# GPIO_EXPANDER_LED.net
KiCad netlist of a schematic drawn in Altium Designer
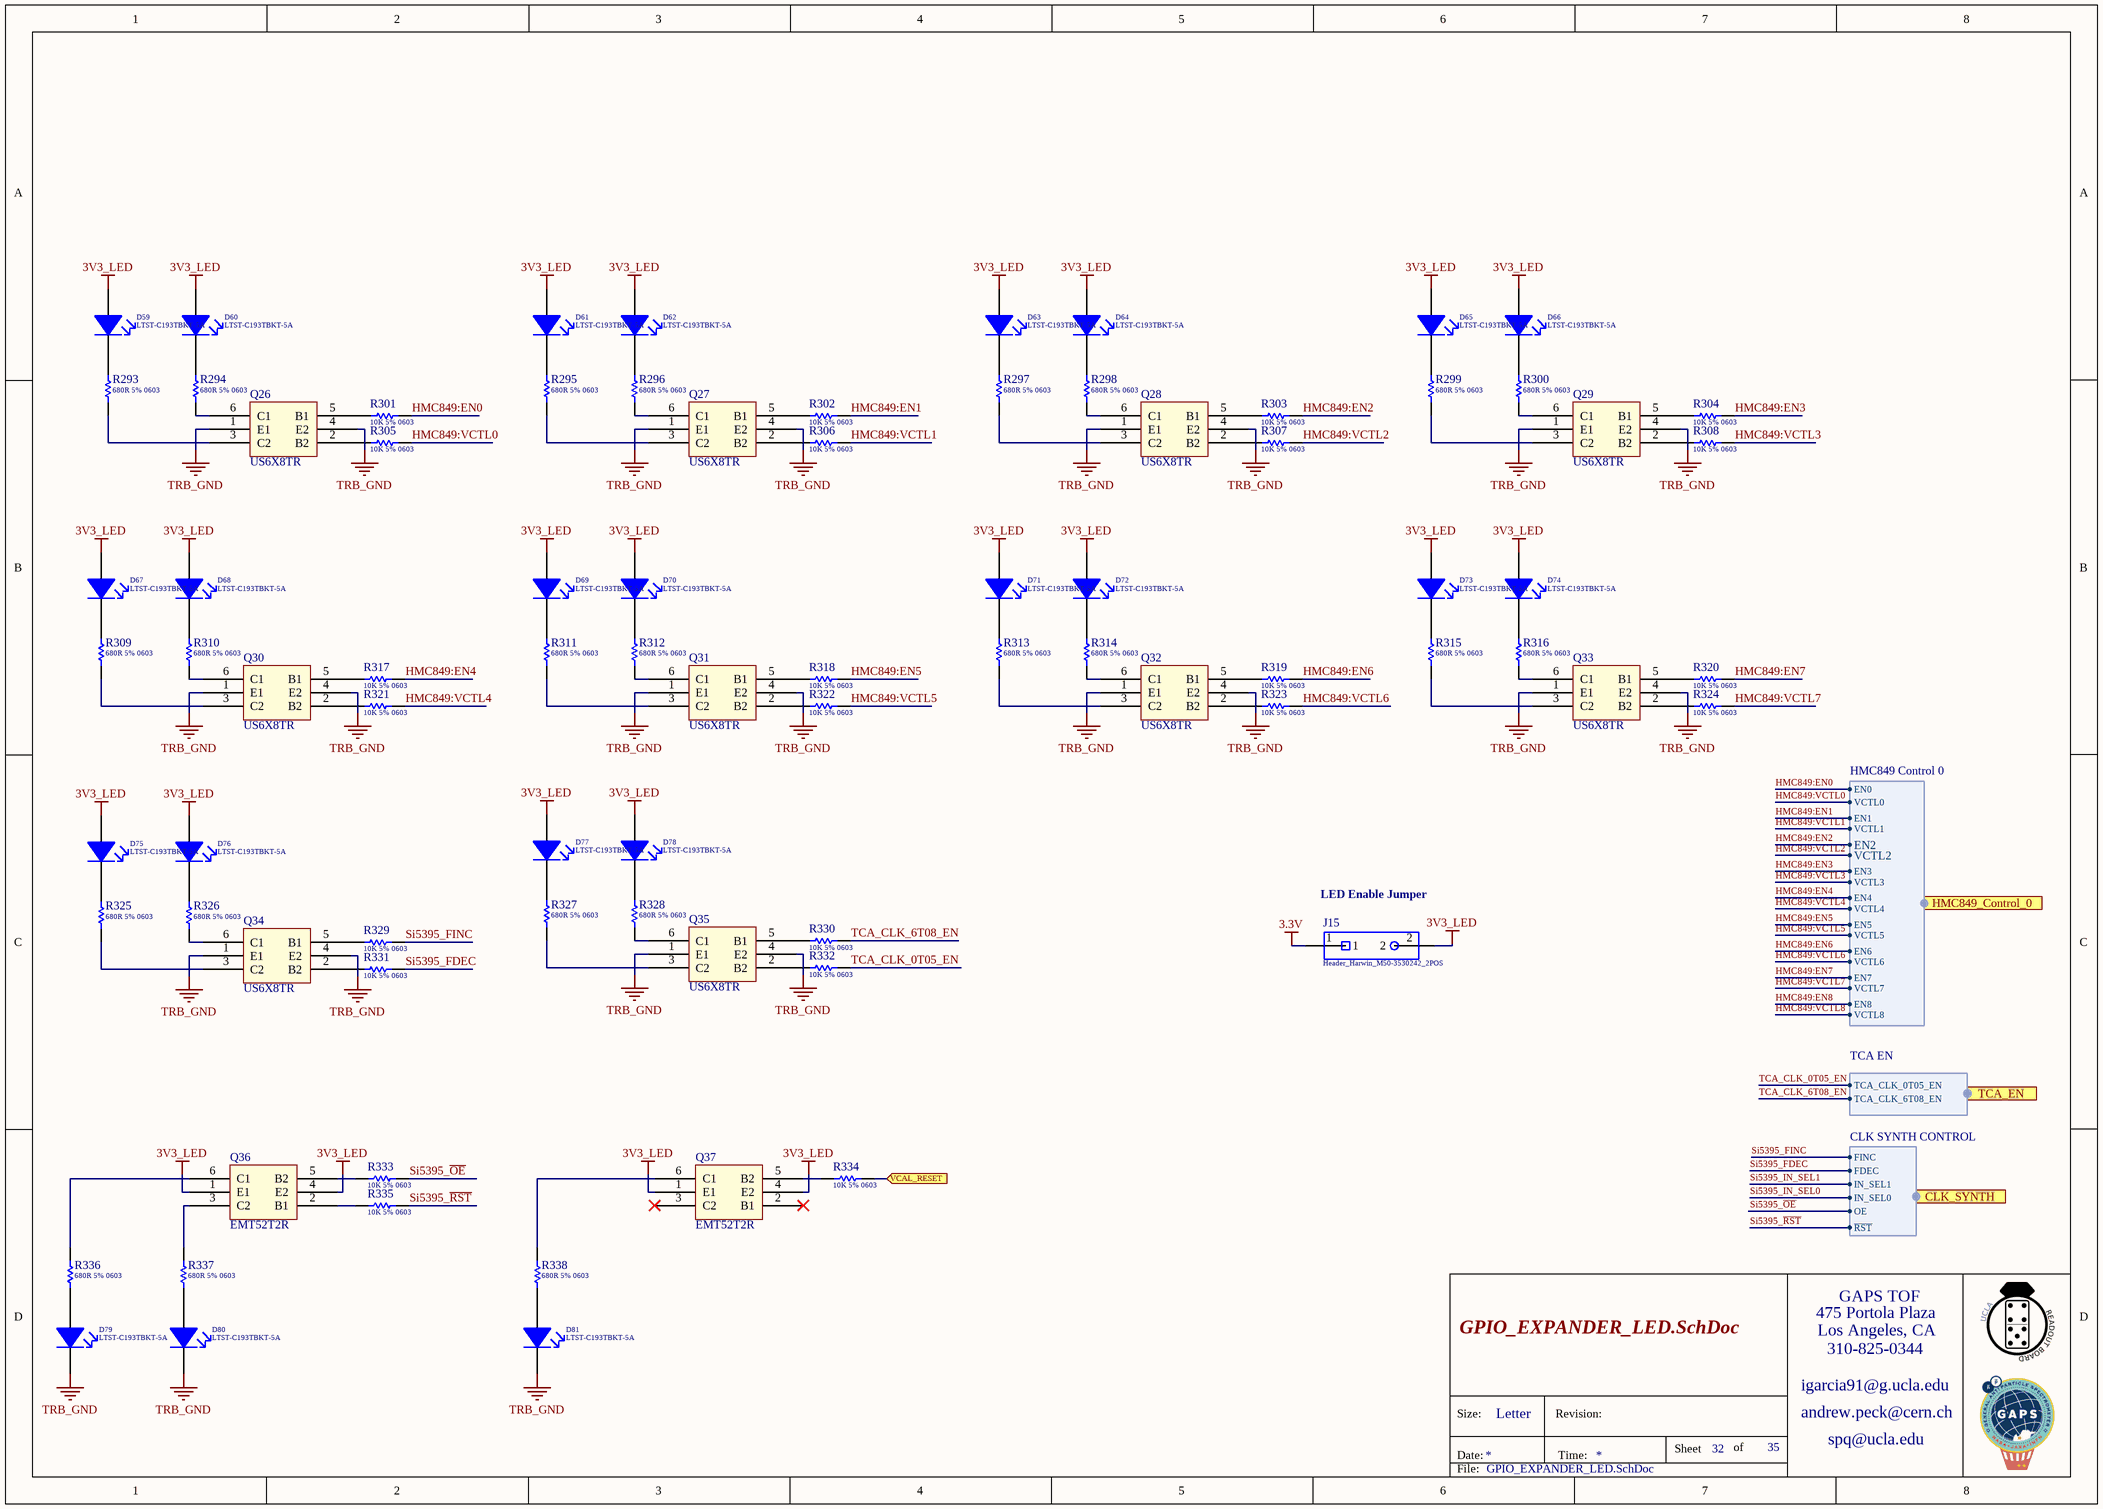
[diagram p0: GPIO_EXPANDER_LED.SchDoc]

(export (version "E")
  (design (tool "Eeschema 10.0.6"))
  (components
    (comp (ref "D59")
      (value "Led_Lite-On_LTST-C193TBKT-5A_Blue")
      (footprint "Led_Lite-On_LTST-C193TBKT-5A_Blue")
      (description "Standard LEDs - SMD Blue 470nm 28mcd 20mA")
      (fields (field (name "SERIES") "LTST-C193TBKT-5A"))
      (libsource (lib "Led_Lite-On_LTST-C193TBKT-5A_Blue") (part "Led_Lite-On_LTST-C193TBKT-5A_Blue"))
    )
    (comp (ref "D60")
      (value "Led_Lite-On_LTST-C193TBKT-5A_Blue")
      (footprint "Led_Lite-On_LTST-C193TBKT-5A_Blue")
      (description "Standard LEDs - SMD Blue 470nm 28mcd 20mA")
      (fields (field (name "SERIES") "LTST-C193TBKT-5A"))
      (libsource (lib "Led_Lite-On_LTST-C193TBKT-5A_Blue") (part "Led_Lite-On_LTST-C193TBKT-5A_Blue"))
    )
    (comp (ref "D61")
      (value "Led_Lite-On_LTST-C193TBKT-5A_Blue")
      (footprint "Led_Lite-On_LTST-C193TBKT-5A_Blue")
      (description "Standard LEDs - SMD Blue 470nm 28mcd 20mA")
      (fields (field (name "SERIES") "LTST-C193TBKT-5A"))
      (libsource (lib "Led_Lite-On_LTST-C193TBKT-5A_Blue") (part "Led_Lite-On_LTST-C193TBKT-5A_Blue"))
    )
    (comp (ref "D62")
      (value "Led_Lite-On_LTST-C193TBKT-5A_Blue")
      (footprint "Led_Lite-On_LTST-C193TBKT-5A_Blue")
      (description "Standard LEDs - SMD Blue 470nm 28mcd 20mA")
      (fields (field (name "SERIES") "LTST-C193TBKT-5A"))
      (libsource (lib "Led_Lite-On_LTST-C193TBKT-5A_Blue") (part "Led_Lite-On_LTST-C193TBKT-5A_Blue"))
    )
    (comp (ref "D63")
      (value "Led_Lite-On_LTST-C193TBKT-5A_Blue")
      (footprint "Led_Lite-On_LTST-C193TBKT-5A_Blue")
      (description "Standard LEDs - SMD Blue 470nm 28mcd 20mA")
      (fields (field (name "SERIES") "LTST-C193TBKT-5A"))
      (libsource (lib "Led_Lite-On_LTST-C193TBKT-5A_Blue") (part "Led_Lite-On_LTST-C193TBKT-5A_Blue"))
    )
    (comp (ref "D64")
      (value "Led_Lite-On_LTST-C193TBKT-5A_Blue")
      (footprint "Led_Lite-On_LTST-C193TBKT-5A_Blue")
      (description "Standard LEDs - SMD Blue 470nm 28mcd 20mA")
      (fields (field (name "SERIES") "LTST-C193TBKT-5A"))
      (libsource (lib "Led_Lite-On_LTST-C193TBKT-5A_Blue") (part "Led_Lite-On_LTST-C193TBKT-5A_Blue"))
    )
    (comp (ref "D65")
      (value "Led_Lite-On_LTST-C193TBKT-5A_Blue")
      (footprint "Led_Lite-On_LTST-C193TBKT-5A_Blue")
      (description "Standard LEDs - SMD Blue 470nm 28mcd 20mA")
      (fields (field (name "SERIES") "LTST-C193TBKT-5A"))
      (libsource (lib "Led_Lite-On_LTST-C193TBKT-5A_Blue") (part "Led_Lite-On_LTST-C193TBKT-5A_Blue"))
    )
    (comp (ref "D66")
      (value "Led_Lite-On_LTST-C193TBKT-5A_Blue")
      (footprint "Led_Lite-On_LTST-C193TBKT-5A_Blue")
      (description "Standard LEDs - SMD Blue 470nm 28mcd 20mA")
      (fields (field (name "SERIES") "LTST-C193TBKT-5A"))
      (libsource (lib "Led_Lite-On_LTST-C193TBKT-5A_Blue") (part "Led_Lite-On_LTST-C193TBKT-5A_Blue"))
    )
    (comp (ref "D67")
      (value "Led_Lite-On_LTST-C193TBKT-5A_Blue")
      (footprint "Led_Lite-On_LTST-C193TBKT-5A_Blue")
      (description "Standard LEDs - SMD Blue 470nm 28mcd 20mA")
      (fields (field (name "SERIES") "LTST-C193TBKT-5A"))
      (libsource (lib "Led_Lite-On_LTST-C193TBKT-5A_Blue") (part "Led_Lite-On_LTST-C193TBKT-5A_Blue"))
    )
    (comp (ref "D68")
      (value "Led_Lite-On_LTST-C193TBKT-5A_Blue")
      (footprint "Led_Lite-On_LTST-C193TBKT-5A_Blue")
      (description "Standard LEDs - SMD Blue 470nm 28mcd 20mA")
      (fields (field (name "SERIES") "LTST-C193TBKT-5A"))
      (libsource (lib "Led_Lite-On_LTST-C193TBKT-5A_Blue") (part "Led_Lite-On_LTST-C193TBKT-5A_Blue"))
    )
    (comp (ref "D69")
      (value "Led_Lite-On_LTST-C193TBKT-5A_Blue")
      (footprint "Led_Lite-On_LTST-C193TBKT-5A_Blue")
      (description "Standard LEDs - SMD Blue 470nm 28mcd 20mA")
      (fields (field (name "SERIES") "LTST-C193TBKT-5A"))
      (libsource (lib "Led_Lite-On_LTST-C193TBKT-5A_Blue") (part "Led_Lite-On_LTST-C193TBKT-5A_Blue"))
    )
    (comp (ref "D70")
      (value "Led_Lite-On_LTST-C193TBKT-5A_Blue")
      (footprint "Led_Lite-On_LTST-C193TBKT-5A_Blue")
      (description "Standard LEDs - SMD Blue 470nm 28mcd 20mA")
      (fields (field (name "SERIES") "LTST-C193TBKT-5A"))
      (libsource (lib "Led_Lite-On_LTST-C193TBKT-5A_Blue") (part "Led_Lite-On_LTST-C193TBKT-5A_Blue"))
    )
    (comp (ref "D71")
      (value "Led_Lite-On_LTST-C193TBKT-5A_Blue")
      (footprint "Led_Lite-On_LTST-C193TBKT-5A_Blue")
      (description "Standard LEDs - SMD Blue 470nm 28mcd 20mA")
      (fields (field (name "SERIES") "LTST-C193TBKT-5A"))
      (libsource (lib "Led_Lite-On_LTST-C193TBKT-5A_Blue") (part "Led_Lite-On_LTST-C193TBKT-5A_Blue"))
    )
    (comp (ref "D72")
      (value "Led_Lite-On_LTST-C193TBKT-5A_Blue")
      (footprint "Led_Lite-On_LTST-C193TBKT-5A_Blue")
      (description "Standard LEDs - SMD Blue 470nm 28mcd 20mA")
      (fields (field (name "SERIES") "LTST-C193TBKT-5A"))
      (libsource (lib "Led_Lite-On_LTST-C193TBKT-5A_Blue") (part "Led_Lite-On_LTST-C193TBKT-5A_Blue"))
    )
    (comp (ref "D73")
      (value "Led_Lite-On_LTST-C193TBKT-5A_Blue")
      (footprint "Led_Lite-On_LTST-C193TBKT-5A_Blue")
      (description "Standard LEDs - SMD Blue 470nm 28mcd 20mA")
      (fields (field (name "SERIES") "LTST-C193TBKT-5A"))
      (libsource (lib "Led_Lite-On_LTST-C193TBKT-5A_Blue") (part "Led_Lite-On_LTST-C193TBKT-5A_Blue"))
    )
    (comp (ref "D74")
      (value "Led_Lite-On_LTST-C193TBKT-5A_Blue")
      (footprint "Led_Lite-On_LTST-C193TBKT-5A_Blue")
      (description "Standard LEDs - SMD Blue 470nm 28mcd 20mA")
      (fields (field (name "SERIES") "LTST-C193TBKT-5A"))
      (libsource (lib "Led_Lite-On_LTST-C193TBKT-5A_Blue") (part "Led_Lite-On_LTST-C193TBKT-5A_Blue"))
    )
    (comp (ref "D75")
      (value "Led_Lite-On_LTST-C193TBKT-5A_Blue")
      (footprint "Led_Lite-On_LTST-C193TBKT-5A_Blue")
      (description "Standard LEDs - SMD Blue 470nm 28mcd 20mA")
      (fields (field (name "SERIES") "LTST-C193TBKT-5A"))
      (libsource (lib "Led_Lite-On_LTST-C193TBKT-5A_Blue") (part "Led_Lite-On_LTST-C193TBKT-5A_Blue"))
    )
    (comp (ref "D76")
      (value "Led_Lite-On_LTST-C193TBKT-5A_Blue")
      (footprint "Led_Lite-On_LTST-C193TBKT-5A_Blue")
      (description "Standard LEDs - SMD Blue 470nm 28mcd 20mA")
      (fields (field (name "SERIES") "LTST-C193TBKT-5A"))
      (libsource (lib "Led_Lite-On_LTST-C193TBKT-5A_Blue") (part "Led_Lite-On_LTST-C193TBKT-5A_Blue"))
    )
    (comp (ref "D77")
      (value "Led_Lite-On_LTST-C193TBKT-5A_Blue")
      (footprint "Led_Lite-On_LTST-C193TBKT-5A_Blue")
      (description "Standard LEDs - SMD Blue 470nm 28mcd 20mA")
      (fields (field (name "SERIES") "LTST-C193TBKT-5A"))
      (libsource (lib "Led_Lite-On_LTST-C193TBKT-5A_Blue") (part "Led_Lite-On_LTST-C193TBKT-5A_Blue"))
    )
    (comp (ref "D78")
      (value "Led_Lite-On_LTST-C193TBKT-5A_Blue")
      (footprint "Led_Lite-On_LTST-C193TBKT-5A_Blue")
      (description "Standard LEDs - SMD Blue 470nm 28mcd 20mA")
      (fields (field (name "SERIES") "LTST-C193TBKT-5A"))
      (libsource (lib "Led_Lite-On_LTST-C193TBKT-5A_Blue") (part "Led_Lite-On_LTST-C193TBKT-5A_Blue"))
    )
    (comp (ref "D79")
      (value "Led_Lite-On_LTST-C193TBKT-5A_Blue")
      (footprint "Led_Lite-On_LTST-C193TBKT-5A_Blue")
      (description "Standard LEDs - SMD Blue 470nm 28mcd 20mA")
      (fields (field (name "SERIES") "LTST-C193TBKT-5A"))
      (libsource (lib "Led_Lite-On_LTST-C193TBKT-5A_Blue") (part "Led_Lite-On_LTST-C193TBKT-5A_Blue"))
    )
    (comp (ref "D80")
      (value "Led_Lite-On_LTST-C193TBKT-5A_Blue")
      (footprint "Led_Lite-On_LTST-C193TBKT-5A_Blue")
      (description "Standard LEDs - SMD Blue 470nm 28mcd 20mA")
      (fields (field (name "SERIES") "LTST-C193TBKT-5A"))
      (libsource (lib "Led_Lite-On_LTST-C193TBKT-5A_Blue") (part "Led_Lite-On_LTST-C193TBKT-5A_Blue"))
    )
    (comp (ref "D81")
      (value "Led_Lite-On_LTST-C193TBKT-5A_Blue")
      (footprint "Led_Lite-On_LTST-C193TBKT-5A_Blue")
      (description "Standard LEDs - SMD Blue 470nm 28mcd 20mA")
      (fields (field (name "SERIES") "LTST-C193TBKT-5A"))
      (libsource (lib "Led_Lite-On_LTST-C193TBKT-5A_Blue") (part "Led_Lite-On_LTST-C193TBKT-5A_Blue"))
    )
    (comp (ref "J15")
      (value "Header_Harwin_M50-3530242_2POS")
      (footprint "Header_Harwin_M50-3530242_2POS")
      (description "Headers & Wire Housings 2 WAY SIL VERT PC TAIL P/HDR")
      (libsource (lib "Header_Harwin_M50-3530242_2POS") (part "Header_Harwin_M50-3530242_2POS"))
    )
    (comp (ref "Q26")
      (value "BJT_ROHM_US6X8TR_1A_NPN")
      (footprint "BJT_ROHM_US6X8TR_1A_NPN")
      (description "Bipolar Transistors - BJT NPN+NPN 30VCEO 1A SOT-363T")
      (fields (field (name "SERIES") "US6X8TR"))
      (libsource (lib "BJT_ROHM_US6X8TR_1A_NPN") (part "BJT_ROHM_US6X8TR_1A_NPN"))
    )
    (comp (ref "Q27")
      (value "BJT_ROHM_US6X8TR_1A_NPN")
      (footprint "BJT_ROHM_US6X8TR_1A_NPN")
      (description "Bipolar Transistors - BJT NPN+NPN 30VCEO 1A SOT-363T")
      (fields (field (name "SERIES") "US6X8TR"))
      (libsource (lib "BJT_ROHM_US6X8TR_1A_NPN") (part "BJT_ROHM_US6X8TR_1A_NPN"))
    )
    (comp (ref "Q28")
      (value "BJT_ROHM_US6X8TR_1A_NPN")
      (footprint "BJT_ROHM_US6X8TR_1A_NPN")
      (description "Bipolar Transistors - BJT NPN+NPN 30VCEO 1A SOT-363T")
      (fields (field (name "SERIES") "US6X8TR"))
      (libsource (lib "BJT_ROHM_US6X8TR_1A_NPN") (part "BJT_ROHM_US6X8TR_1A_NPN"))
    )
    (comp (ref "Q29")
      (value "BJT_ROHM_US6X8TR_1A_NPN")
      (footprint "BJT_ROHM_US6X8TR_1A_NPN")
      (description "Bipolar Transistors - BJT NPN+NPN 30VCEO 1A SOT-363T")
      (fields (field (name "SERIES") "US6X8TR"))
      (libsource (lib "BJT_ROHM_US6X8TR_1A_NPN") (part "BJT_ROHM_US6X8TR_1A_NPN"))
    )
    (comp (ref "Q30")
      (value "BJT_ROHM_US6X8TR_1A_NPN")
      (footprint "BJT_ROHM_US6X8TR_1A_NPN")
      (description "Bipolar Transistors - BJT NPN+NPN 30VCEO 1A SOT-363T")
      (fields (field (name "SERIES") "US6X8TR"))
      (libsource (lib "BJT_ROHM_US6X8TR_1A_NPN") (part "BJT_ROHM_US6X8TR_1A_NPN"))
    )
    (comp (ref "Q31")
      (value "BJT_ROHM_US6X8TR_1A_NPN")
      (footprint "BJT_ROHM_US6X8TR_1A_NPN")
      (description "Bipolar Transistors - BJT NPN+NPN 30VCEO 1A SOT-363T")
      (fields (field (name "SERIES") "US6X8TR"))
      (libsource (lib "BJT_ROHM_US6X8TR_1A_NPN") (part "BJT_ROHM_US6X8TR_1A_NPN"))
    )
    (comp (ref "Q32")
      (value "BJT_ROHM_US6X8TR_1A_NPN")
      (footprint "BJT_ROHM_US6X8TR_1A_NPN")
      (description "Bipolar Transistors - BJT NPN+NPN 30VCEO 1A SOT-363T")
      (fields (field (name "SERIES") "US6X8TR"))
      (libsource (lib "BJT_ROHM_US6X8TR_1A_NPN") (part "BJT_ROHM_US6X8TR_1A_NPN"))
    )
    (comp (ref "Q33")
      (value "BJT_ROHM_US6X8TR_1A_NPN")
      (footprint "BJT_ROHM_US6X8TR_1A_NPN")
      (description "Bipolar Transistors - BJT NPN+NPN 30VCEO 1A SOT-363T")
      (fields (field (name "SERIES") "US6X8TR"))
      (libsource (lib "BJT_ROHM_US6X8TR_1A_NPN") (part "BJT_ROHM_US6X8TR_1A_NPN"))
    )
    (comp (ref "Q34")
      (value "BJT_ROHM_US6X8TR_1A_NPN")
      (footprint "BJT_ROHM_US6X8TR_1A_NPN")
      (description "Bipolar Transistors - BJT NPN+NPN 30VCEO 1A SOT-363T")
      (fields (field (name "SERIES") "US6X8TR"))
      (libsource (lib "BJT_ROHM_US6X8TR_1A_NPN") (part "BJT_ROHM_US6X8TR_1A_NPN"))
    )
    (comp (ref "Q35")
      (value "BJT_ROHM_US6X8TR_1A_NPN")
      (footprint "BJT_ROHM_US6X8TR_1A_NPN")
      (description "Bipolar Transistors - BJT NPN+NPN 30VCEO 1A SOT-363T")
      (fields (field (name "SERIES") "US6X8TR"))
      (libsource (lib "BJT_ROHM_US6X8TR_1A_NPN") (part "BJT_ROHM_US6X8TR_1A_NPN"))
    )
    (comp (ref "Q36")
      (value "BJT_ROHM_EMT52T2R_100mA_PNP")
      (footprint "BJT_ROHM_EMT52T2R_100mA_PNP")
      (description "Bipolar Transistors - BJT Bipolar Transistor SOT-563 SC-107C EMT6")
      (fields (field (name "SERIES") "EMT52T2R"))
      (libsource (lib "BJT_ROHM_EMT52T2R_100mA_PNP") (part "BJT_ROHM_EMT52T2R_100mA_PNP"))
    )
    (comp (ref "Q37")
      (value "BJT_ROHM_EMT52T2R_100mA_PNP")
      (footprint "BJT_ROHM_EMT52T2R_100mA_PNP")
      (description "Bipolar Transistors - BJT Bipolar Transistor SOT-563 SC-107C EMT6")
      (fields (field (name "SERIES") "EMT52T2R"))
      (libsource (lib "BJT_ROHM_EMT52T2R_100mA_PNP") (part "BJT_ROHM_EMT52T2R_100mA_PNP"))
    )
    (comp (ref "R293")
      (value "680R 5% 0603")
      (footprint "RESC0603(1608)_L")
      (description "680R 0.1W 5% 0603 (1608 Metric)  SMD")
      (fields (field (name "TOLERANCE") "5 %") (field (name "POWER") "0.1 W"))
      (libsource (lib "Altium Content Vault") (part "RES"))
    )
    (comp (ref "R294")
      (value "680R 5% 0603")
      (footprint "RESC0603(1608)_L")
      (description "680R 0.1W 5% 0603 (1608 Metric)  SMD")
      (fields (field (name "TOLERANCE") "5 %") (field (name "POWER") "0.1 W"))
      (libsource (lib "Altium Content Vault") (part "RES"))
    )
    (comp (ref "R295")
      (value "680R 5% 0603")
      (footprint "RESC0603(1608)_L")
      (description "680R 0.1W 5% 0603 (1608 Metric)  SMD")
      (fields (field (name "TOLERANCE") "5 %") (field (name "POWER") "0.1 W"))
      (libsource (lib "Altium Content Vault") (part "RES"))
    )
    (comp (ref "R296")
      (value "680R 5% 0603")
      (footprint "RESC0603(1608)_L")
      (description "680R 0.1W 5% 0603 (1608 Metric)  SMD")
      (fields (field (name "TOLERANCE") "5 %") (field (name "POWER") "0.1 W"))
      (libsource (lib "Altium Content Vault") (part "RES"))
    )
    (comp (ref "R297")
      (value "680R 5% 0603")
      (footprint "RESC0603(1608)_L")
      (description "680R 0.1W 5% 0603 (1608 Metric)  SMD")
      (fields (field (name "TOLERANCE") "5 %") (field (name "POWER") "0.1 W"))
      (libsource (lib "Altium Content Vault") (part "RES"))
    )
    (comp (ref "R298")
      (value "680R 5% 0603")
      (footprint "RESC0603(1608)_L")
      (description "680R 0.1W 5% 0603 (1608 Metric)  SMD")
      (fields (field (name "TOLERANCE") "5 %") (field (name "POWER") "0.1 W"))
      (libsource (lib "Altium Content Vault") (part "RES"))
    )
    (comp (ref "R299")
      (value "680R 5% 0603")
      (footprint "RESC0603(1608)_L")
      (description "680R 0.1W 5% 0603 (1608 Metric)  SMD")
      (fields (field (name "TOLERANCE") "5 %") (field (name "POWER") "0.1 W"))
      (libsource (lib "Altium Content Vault") (part "RES"))
    )
    (comp (ref "R300")
      (value "680R 5% 0603")
      (footprint "RESC0603(1608)_L")
      (description "680R 0.1W 5% 0603 (1608 Metric)  SMD")
      (fields (field (name "TOLERANCE") "5 %") (field (name "POWER") "0.1 W"))
      (libsource (lib "Altium Content Vault") (part "RES"))
    )
    (comp (ref "R301")
      (value "10K 5% 0603")
      (footprint "RESC0603(1608)_L")
      (description "10K 0.1W 5% 0603 (1608 Metric)  SMD")
      (fields (field (name "TOLERANCE") "5 %") (field (name "POWER") "0.1 W"))
      (libsource (lib "Altium Content Vault") (part "RES"))
    )
    (comp (ref "R302")
      (value "10K 5% 0603")
      (footprint "RESC0603(1608)_L")
      (description "10K 0.1W 5% 0603 (1608 Metric)  SMD")
      (fields (field (name "TOLERANCE") "5 %") (field (name "POWER") "0.1 W"))
      (libsource (lib "Altium Content Vault") (part "RES"))
    )
    (comp (ref "R303")
      (value "10K 5% 0603")
      (footprint "RESC0603(1608)_L")
      (description "10K 0.1W 5% 0603 (1608 Metric)  SMD")
      (fields (field (name "TOLERANCE") "5 %") (field (name "POWER") "0.1 W"))
      (libsource (lib "Altium Content Vault") (part "RES"))
    )
    (comp (ref "R304")
      (value "10K 5% 0603")
      (footprint "RESC0603(1608)_L")
      (description "10K 0.1W 5% 0603 (1608 Metric)  SMD")
      (fields (field (name "TOLERANCE") "5 %") (field (name "POWER") "0.1 W"))
      (libsource (lib "Altium Content Vault") (part "RES"))
    )
    (comp (ref "R305")
      (value "10K 5% 0603")
      (footprint "RESC0603(1608)_L")
      (description "10K 0.1W 5% 0603 (1608 Metric)  SMD")
      (fields (field (name "TOLERANCE") "5 %") (field (name "POWER") "0.1 W"))
      (libsource (lib "Altium Content Vault") (part "RES"))
    )
    (comp (ref "R306")
      (value "10K 5% 0603")
      (footprint "RESC0603(1608)_L")
      (description "10K 0.1W 5% 0603 (1608 Metric)  SMD")
      (fields (field (name "TOLERANCE") "5 %") (field (name "POWER") "0.1 W"))
      (libsource (lib "Altium Content Vault") (part "RES"))
    )
    (comp (ref "R307")
      (value "10K 5% 0603")
      (footprint "RESC0603(1608)_L")
      (description "10K 0.1W 5% 0603 (1608 Metric)  SMD")
      (fields (field (name "TOLERANCE") "5 %") (field (name "POWER") "0.1 W"))
      (libsource (lib "Altium Content Vault") (part "RES"))
    )
    (comp (ref "R308")
      (value "10K 5% 0603")
      (footprint "RESC0603(1608)_L")
      (description "10K 0.1W 5% 0603 (1608 Metric)  SMD")
      (fields (field (name "TOLERANCE") "5 %") (field (name "POWER") "0.1 W"))
      (libsource (lib "Altium Content Vault") (part "RES"))
    )
    (comp (ref "R309")
      (value "680R 5% 0603")
      (footprint "RESC0603(1608)_L")
      (description "680R 0.1W 5% 0603 (1608 Metric)  SMD")
      (fields (field (name "TOLERANCE") "5 %") (field (name "POWER") "0.1 W"))
      (libsource (lib "Altium Content Vault") (part "RES"))
    )
    (comp (ref "R310")
      (value "680R 5% 0603")
      (footprint "RESC0603(1608)_L")
      (description "680R 0.1W 5% 0603 (1608 Metric)  SMD")
      (fields (field (name "TOLERANCE") "5 %") (field (name "POWER") "0.1 W"))
      (libsource (lib "Altium Content Vault") (part "RES"))
    )
    (comp (ref "R311")
      (value "680R 5% 0603")
      (footprint "RESC0603(1608)_L")
      (description "680R 0.1W 5% 0603 (1608 Metric)  SMD")
      (fields (field (name "TOLERANCE") "5 %") (field (name "POWER") "0.1 W"))
      (libsource (lib "Altium Content Vault") (part "RES"))
    )
    (comp (ref "R312")
      (value "680R 5% 0603")
      (footprint "RESC0603(1608)_L")
      (description "680R 0.1W 5% 0603 (1608 Metric)  SMD")
      (fields (field (name "TOLERANCE") "5 %") (field (name "POWER") "0.1 W"))
      (libsource (lib "Altium Content Vault") (part "RES"))
    )
    (comp (ref "R313")
      (value "680R 5% 0603")
      (footprint "RESC0603(1608)_L")
      (description "680R 0.1W 5% 0603 (1608 Metric)  SMD")
      (fields (field (name "TOLERANCE") "5 %") (field (name "POWER") "0.1 W"))
      (libsource (lib "Altium Content Vault") (part "RES"))
    )
    (comp (ref "R314")
      (value "680R 5% 0603")
      (footprint "RESC0603(1608)_L")
      (description "680R 0.1W 5% 0603 (1608 Metric)  SMD")
      (fields (field (name "TOLERANCE") "5 %") (field (name "POWER") "0.1 W"))
      (libsource (lib "Altium Content Vault") (part "RES"))
    )
    (comp (ref "R315")
      (value "680R 5% 0603")
      (footprint "RESC0603(1608)_L")
      (description "680R 0.1W 5% 0603 (1608 Metric)  SMD")
      (fields (field (name "TOLERANCE") "5 %") (field (name "POWER") "0.1 W"))
      (libsource (lib "Altium Content Vault") (part "RES"))
    )
    (comp (ref "R316")
      (value "680R 5% 0603")
      (footprint "RESC0603(1608)_L")
      (description "680R 0.1W 5% 0603 (1608 Metric)  SMD")
      (fields (field (name "TOLERANCE") "5 %") (field (name "POWER") "0.1 W"))
      (libsource (lib "Altium Content Vault") (part "RES"))
    )
    (comp (ref "R317")
      (value "10K 5% 0603")
      (footprint "RESC0603(1608)_L")
      (description "10K 0.1W 5% 0603 (1608 Metric)  SMD")
      (fields (field (name "TOLERANCE") "5 %") (field (name "POWER") "0.1 W"))
      (libsource (lib "Altium Content Vault") (part "RES"))
    )
    (comp (ref "R318")
      (value "10K 5% 0603")
      (footprint "RESC0603(1608)_L")
      (description "10K 0.1W 5% 0603 (1608 Metric)  SMD")
      (fields (field (name "TOLERANCE") "5 %") (field (name "POWER") "0.1 W"))
      (libsource (lib "Altium Content Vault") (part "RES"))
    )
    (comp (ref "R319")
      (value "10K 5% 0603")
      (footprint "RESC0603(1608)_L")
      (description "10K 0.1W 5% 0603 (1608 Metric)  SMD")
      (fields (field (name "TOLERANCE") "5 %") (field (name "POWER") "0.1 W"))
      (libsource (lib "Altium Content Vault") (part "RES"))
    )
    (comp (ref "R320")
      (value "10K 5% 0603")
      (footprint "RESC0603(1608)_L")
      (description "10K 0.1W 5% 0603 (1608 Metric)  SMD")
      (fields (field (name "TOLERANCE") "5 %") (field (name "POWER") "0.1 W"))
      (libsource (lib "Altium Content Vault") (part "RES"))
    )
    (comp (ref "R321")
      (value "10K 5% 0603")
      (footprint "RESC0603(1608)_L")
      (description "10K 0.1W 5% 0603 (1608 Metric)  SMD")
      (fields (field (name "TOLERANCE") "5 %") (field (name "POWER") "0.1 W"))
      (libsource (lib "Altium Content Vault") (part "RES"))
    )
    (comp (ref "R322")
      (value "10K 5% 0603")
      (footprint "RESC0603(1608)_L")
      (description "10K 0.1W 5% 0603 (1608 Metric)  SMD")
      (fields (field (name "TOLERANCE") "5 %") (field (name "POWER") "0.1 W"))
      (libsource (lib "Altium Content Vault") (part "RES"))
    )
    (comp (ref "R323")
      (value "10K 5% 0603")
      (footprint "RESC0603(1608)_L")
      (description "10K 0.1W 5% 0603 (1608 Metric)  SMD")
      (fields (field (name "TOLERANCE") "5 %") (field (name "POWER") "0.1 W"))
      (libsource (lib "Altium Content Vault") (part "RES"))
    )
    (comp (ref "R324")
      (value "10K 5% 0603")
      (footprint "RESC0603(1608)_L")
      (description "10K 0.1W 5% 0603 (1608 Metric)  SMD")
      (fields (field (name "TOLERANCE") "5 %") (field (name "POWER") "0.1 W"))
      (libsource (lib "Altium Content Vault") (part "RES"))
    )
    (comp (ref "R325")
      (value "680R 5% 0603")
      (footprint "RESC0603(1608)_L")
      (description "680R 0.1W 5% 0603 (1608 Metric)  SMD")
      (fields (field (name "TOLERANCE") "5 %") (field (name "POWER") "0.1 W"))
      (libsource (lib "Altium Content Vault") (part "RES"))
    )
    (comp (ref "R326")
      (value "680R 5% 0603")
      (footprint "RESC0603(1608)_L")
      (description "680R 0.1W 5% 0603 (1608 Metric)  SMD")
      (fields (field (name "TOLERANCE") "5 %") (field (name "POWER") "0.1 W"))
      (libsource (lib "Altium Content Vault") (part "RES"))
    )
    (comp (ref "R327")
      (value "680R 5% 0603")
      (footprint "RESC0603(1608)_L")
      (description "680R 0.1W 5% 0603 (1608 Metric)  SMD")
      (fields (field (name "TOLERANCE") "5 %") (field (name "POWER") "0.1 W"))
      (libsource (lib "Altium Content Vault") (part "RES"))
    )
    (comp (ref "R328")
      (value "680R 5% 0603")
      (footprint "RESC0603(1608)_L")
      (description "680R 0.1W 5% 0603 (1608 Metric)  SMD")
      (fields (field (name "TOLERANCE") "5 %") (field (name "POWER") "0.1 W"))
      (libsource (lib "Altium Content Vault") (part "RES"))
    )
    (comp (ref "R329")
      (value "10K 5% 0603")
      (footprint "RESC0603(1608)_L")
      (description "10K 0.1W 5% 0603 (1608 Metric)  SMD")
      (fields (field (name "TOLERANCE") "5 %") (field (name "POWER") "0.1 W"))
      (libsource (lib "Altium Content Vault") (part "RES"))
    )
    (comp (ref "R330")
      (value "10K 5% 0603")
      (footprint "RESC0603(1608)_L")
      (description "10K 0.1W 5% 0603 (1608 Metric)  SMD")
      (fields (field (name "TOLERANCE") "5 %") (field (name "POWER") "0.1 W"))
      (libsource (lib "Altium Content Vault") (part "RES"))
    )
    (comp (ref "R331")
      (value "10K 5% 0603")
      (footprint "RESC0603(1608)_L")
      (description "10K 0.1W 5% 0603 (1608 Metric)  SMD")
      (fields (field (name "TOLERANCE") "5 %") (field (name "POWER") "0.1 W"))
      (libsource (lib "Altium Content Vault") (part "RES"))
    )
    (comp (ref "R332")
      (value "10K 5% 0603")
      (footprint "RESC0603(1608)_L")
      (description "10K 0.1W 5% 0603 (1608 Metric)  SMD")
      (fields (field (name "TOLERANCE") "5 %") (field (name "POWER") "0.1 W"))
      (libsource (lib "Altium Content Vault") (part "RES"))
    )
    (comp (ref "R333")
      (value "10K 5% 0603")
      (footprint "RESC0603(1608)_L")
      (description "10K 0.1W 5% 0603 (1608 Metric)  SMD")
      (fields (field (name "TOLERANCE") "5 %") (field (name "POWER") "0.1 W"))
      (libsource (lib "Altium Content Vault") (part "RES"))
    )
    (comp (ref "R334")
      (value "10K 5% 0603")
      (footprint "RESC0603(1608)_L")
      (description "10K 0.1W 5% 0603 (1608 Metric)  SMD")
      (fields (field (name "TOLERANCE") "5 %") (field (name "POWER") "0.1 W"))
      (libsource (lib "Altium Content Vault") (part "RES"))
    )
    (comp (ref "R335")
      (value "10K 5% 0603")
      (footprint "RESC0603(1608)_L")
      (description "10K 0.1W 5% 0603 (1608 Metric)  SMD")
      (fields (field (name "TOLERANCE") "5 %") (field (name "POWER") "0.1 W"))
      (libsource (lib "Altium Content Vault") (part "RES"))
    )
    (comp (ref "R336")
      (value "680R 5% 0603")
      (footprint "RESC0603(1608)_L")
      (description "680R 0.1W 5% 0603 (1608 Metric)  SMD")
      (fields (field (name "TOLERANCE") "5 %") (field (name "POWER") "0.1 W"))
      (libsource (lib "Altium Content Vault") (part "RES"))
    )
    (comp (ref "R337")
      (value "680R 5% 0603")
      (footprint "RESC0603(1608)_L")
      (description "680R 0.1W 5% 0603 (1608 Metric)  SMD")
      (fields (field (name "TOLERANCE") "5 %") (field (name "POWER") "0.1 W"))
      (libsource (lib "Altium Content Vault") (part "RES"))
    )
    (comp (ref "R338")
      (value "680R 5% 0603")
      (footprint "RESC0603(1608)_L")
      (description "680R 0.1W 5% 0603 (1608 Metric)  SMD")
      (fields (field (name "TOLERANCE") "5 %") (field (name "POWER") "0.1 W"))
      (libsource (lib "Altium Content Vault") (part "RES"))
    )
  )
  (nets
    (net (code "9") (name "/HMC849:EN0") (class "Default")
      (node (ref "R301") (pin "2") (pinfunction "2_2") (pintype "passive"))
    )
    (net (code "10") (name "/HMC849:EN1") (class "Default")
      (node (ref "R302") (pin "2") (pinfunction "2_2") (pintype "passive"))
    )
    (net (code "11") (name "/HMC849:EN2") (class "Default")
      (node (ref "R303") (pin "2") (pinfunction "2_2") (pintype "passive"))
    )
    (net (code "12") (name "/HMC849:EN3") (class "Default")
      (node (ref "R304") (pin "2") (pinfunction "2_2") (pintype "passive"))
    )
    (net (code "13") (name "/HMC849:EN4") (class "Default")
      (node (ref "R317") (pin "2") (pinfunction "2_2") (pintype "passive"))
    )
    (net (code "14") (name "/HMC849:EN5") (class "Default")
      (node (ref "R318") (pin "2") (pinfunction "2_2") (pintype "passive"))
    )
    (net (code "15") (name "/HMC849:EN6") (class "Default")
      (node (ref "R319") (pin "2") (pinfunction "2_2") (pintype "passive"))
    )
    (net (code "16") (name "/HMC849:EN7") (class "Default")
      (node (ref "R320") (pin "2") (pinfunction "2_2") (pintype "passive"))
    )
    (net (code "18") (name "/HMC849:VCTL0") (class "Default")
      (node (ref "R305") (pin "1") (pinfunction "1_1") (pintype "passive"))
    )
    (net (code "19") (name "/HMC849:VCTL1") (class "Default")
      (node (ref "R306") (pin "1") (pinfunction "1_1") (pintype "passive"))
    )
    (net (code "20") (name "/HMC849:VCTL2") (class "Default")
      (node (ref "R307") (pin "1") (pinfunction "1_1") (pintype "passive"))
    )
    (net (code "21") (name "/HMC849:VCTL3") (class "Default")
      (node (ref "R308") (pin "1") (pinfunction "1_1") (pintype "passive"))
    )
    (net (code "22") (name "/HMC849:VCTL4") (class "Default")
      (node (ref "R321") (pin "1") (pinfunction "1_1") (pintype "passive"))
    )
    (net (code "23") (name "/HMC849:VCTL5") (class "Default")
      (node (ref "R322") (pin "1") (pinfunction "1_1") (pintype "passive"))
    )
    (net (code "24") (name "/HMC849:VCTL6") (class "Default")
      (node (ref "R323") (pin "1") (pinfunction "1_1") (pintype "passive"))
    )
    (net (code "25") (name "/HMC849:VCTL7") (class "Default")
      (node (ref "R324") (pin "1") (pinfunction "1_1") (pintype "passive"))
    )
    (net (code "27") (name "/Si5395_FDEC") (class "Default")
      (node (ref "R331") (pin "1") (pinfunction "1_1") (pintype "passive"))
    )
    (net (code "28") (name "/Si5395_FINC") (class "Default")
      (node (ref "R329") (pin "2") (pinfunction "2_2") (pintype "passive"))
    )
    (net (code "31") (name "/Si5395_~{OE}") (class "Default")
      (node (ref "R333") (pin "1") (pinfunction "1_1") (pintype "passive"))
    )
    (net (code "32") (name "/Si5395_~{RST}") (class "Default")
      (node (ref "R335") (pin "2") (pinfunction "2_2") (pintype "passive"))
    )
    (net (code "33") (name "/TCA_CLK_0T05_EN") (class "Default")
      (node (ref "R332") (pin "1") (pinfunction "1_1") (pintype "passive"))
    )
    (net (code "34") (name "/TCA_CLK_6T08_EN") (class "Default")
      (node (ref "R330") (pin "2") (pinfunction "2_2") (pintype "passive"))
    )
    (net (code "35") (name "/VCAL_RESET") (class "Default")
      (node (ref "R334") (pin "1") (pinfunction "1_1") (pintype "passive"))
    )
    (net (code "39") (name "3.3V") (class "Default")
      (node (ref "J15") (pin "1") (pinfunction "1_1") (pintype "passive"))
    )
    (net (code "40") (name "3V3_LED") (class "Default")
      (node (ref "D59") (pin "2") (pinfunction "A_2") (pintype "passive"))
      (node (ref "D60") (pin "2") (pinfunction "A_2") (pintype "passive"))
      (node (ref "D61") (pin "2") (pinfunction "A_2") (pintype "passive"))
      (node (ref "D62") (pin "2") (pinfunction "A_2") (pintype "passive"))
      (node (ref "D63") (pin "2") (pinfunction "A_2") (pintype "passive"))
      (node (ref "D64") (pin "2") (pinfunction "A_2") (pintype "passive"))
      (node (ref "D65") (pin "2") (pinfunction "A_2") (pintype "passive"))
      (node (ref "D66") (pin "2") (pinfunction "A_2") (pintype "passive"))
      (node (ref "D67") (pin "2") (pinfunction "A_2") (pintype "passive"))
      (node (ref "D68") (pin "2") (pinfunction "A_2") (pintype "passive"))
      (node (ref "D69") (pin "2") (pinfunction "A_2") (pintype "passive"))
      (node (ref "D70") (pin "2") (pinfunction "A_2") (pintype "passive"))
      (node (ref "D71") (pin "2") (pinfunction "A_2") (pintype "passive"))
      (node (ref "D72") (pin "2") (pinfunction "A_2") (pintype "passive"))
      (node (ref "D73") (pin "2") (pinfunction "A_2") (pintype "passive"))
      (node (ref "D74") (pin "2") (pinfunction "A_2") (pintype "passive"))
      (node (ref "D75") (pin "2") (pinfunction "A_2") (pintype "passive"))
      (node (ref "D76") (pin "2") (pinfunction "A_2") (pintype "passive"))
      (node (ref "D77") (pin "2") (pinfunction "A_2") (pintype "passive"))
      (node (ref "D78") (pin "2") (pinfunction "A_2") (pintype "passive"))
      (node (ref "J15") (pin "2") (pinfunction "2_2") (pintype "passive"))
      (node (ref "Q36") (pin "1") (pinfunction "E1_1") (pintype "passive"))
      (node (ref "Q36") (pin "4") (pinfunction "E2_4") (pintype "passive"))
      (node (ref "Q37") (pin "1") (pinfunction "E1_1") (pintype "passive"))
      (node (ref "Q37") (pin "4") (pinfunction "E2_4") (pintype "passive"))
    )
    (net (code "41") (name "Net-(D59-K)") (class "Default")
      (node (ref "D59") (pin "1") (pinfunction "K_1") (pintype "passive"))
      (node (ref "R293") (pin "2") (pinfunction "2_2") (pintype "passive"))
    )
    (net (code "42") (name "Net-(D60-K)") (class "Default")
      (node (ref "D60") (pin "1") (pinfunction "K_1") (pintype "passive"))
      (node (ref "R294") (pin "2") (pinfunction "2_2") (pintype "passive"))
    )
    (net (code "43") (name "Net-(D61-K)") (class "Default")
      (node (ref "D61") (pin "1") (pinfunction "K_1") (pintype "passive"))
      (node (ref "R295") (pin "2") (pinfunction "2_2") (pintype "passive"))
    )
    (net (code "44") (name "Net-(D62-K)") (class "Default")
      (node (ref "D62") (pin "1") (pinfunction "K_1") (pintype "passive"))
      (node (ref "R296") (pin "2") (pinfunction "2_2") (pintype "passive"))
    )
    (net (code "45") (name "Net-(D63-K)") (class "Default")
      (node (ref "D63") (pin "1") (pinfunction "K_1") (pintype "passive"))
      (node (ref "R297") (pin "2") (pinfunction "2_2") (pintype "passive"))
    )
    (net (code "46") (name "Net-(D64-K)") (class "Default")
      (node (ref "D64") (pin "1") (pinfunction "K_1") (pintype "passive"))
      (node (ref "R298") (pin "2") (pinfunction "2_2") (pintype "passive"))
    )
    (net (code "47") (name "Net-(D65-K)") (class "Default")
      (node (ref "D65") (pin "1") (pinfunction "K_1") (pintype "passive"))
      (node (ref "R299") (pin "2") (pinfunction "2_2") (pintype "passive"))
    )
    (net (code "48") (name "Net-(D66-K)") (class "Default")
      (node (ref "D66") (pin "1") (pinfunction "K_1") (pintype "passive"))
      (node (ref "R300") (pin "2") (pinfunction "2_2") (pintype "passive"))
    )
    (net (code "49") (name "Net-(D67-K)") (class "Default")
      (node (ref "D67") (pin "1") (pinfunction "K_1") (pintype "passive"))
      (node (ref "R309") (pin "2") (pinfunction "2_2") (pintype "passive"))
    )
    (net (code "50") (name "Net-(D68-K)") (class "Default")
      (node (ref "D68") (pin "1") (pinfunction "K_1") (pintype "passive"))
      (node (ref "R310") (pin "2") (pinfunction "2_2") (pintype "passive"))
    )
    (net (code "51") (name "Net-(D69-K)") (class "Default")
      (node (ref "D69") (pin "1") (pinfunction "K_1") (pintype "passive"))
      (node (ref "R311") (pin "2") (pinfunction "2_2") (pintype "passive"))
    )
    (net (code "52") (name "Net-(D70-K)") (class "Default")
      (node (ref "D70") (pin "1") (pinfunction "K_1") (pintype "passive"))
      (node (ref "R312") (pin "2") (pinfunction "2_2") (pintype "passive"))
    )
    (net (code "53") (name "Net-(D71-K)") (class "Default")
      (node (ref "D71") (pin "1") (pinfunction "K_1") (pintype "passive"))
      (node (ref "R313") (pin "2") (pinfunction "2_2") (pintype "passive"))
    )
    (net (code "54") (name "Net-(D72-K)") (class "Default")
      (node (ref "D72") (pin "1") (pinfunction "K_1") (pintype "passive"))
      (node (ref "R314") (pin "2") (pinfunction "2_2") (pintype "passive"))
    )
    (net (code "55") (name "Net-(D73-K)") (class "Default")
      (node (ref "D73") (pin "1") (pinfunction "K_1") (pintype "passive"))
      (node (ref "R315") (pin "2") (pinfunction "2_2") (pintype "passive"))
    )
    (net (code "56") (name "Net-(D74-K)") (class "Default")
      (node (ref "D74") (pin "1") (pinfunction "K_1") (pintype "passive"))
      (node (ref "R316") (pin "2") (pinfunction "2_2") (pintype "passive"))
    )
    (net (code "57") (name "Net-(D75-K)") (class "Default")
      (node (ref "D75") (pin "1") (pinfunction "K_1") (pintype "passive"))
      (node (ref "R325") (pin "2") (pinfunction "2_2") (pintype "passive"))
    )
    (net (code "58") (name "Net-(D76-K)") (class "Default")
      (node (ref "D76") (pin "1") (pinfunction "K_1") (pintype "passive"))
      (node (ref "R326") (pin "2") (pinfunction "2_2") (pintype "passive"))
    )
    (net (code "59") (name "Net-(D77-K)") (class "Default")
      (node (ref "D77") (pin "1") (pinfunction "K_1") (pintype "passive"))
      (node (ref "R327") (pin "2") (pinfunction "2_2") (pintype "passive"))
    )
    (net (code "60") (name "Net-(D78-K)") (class "Default")
      (node (ref "D78") (pin "1") (pinfunction "K_1") (pintype "passive"))
      (node (ref "R328") (pin "2") (pinfunction "2_2") (pintype "passive"))
    )
    (net (code "61") (name "Net-(D79-A)") (class "Default")
      (node (ref "D79") (pin "2") (pinfunction "A_2") (pintype "passive"))
      (node (ref "R336") (pin "1") (pinfunction "1_1") (pintype "passive"))
    )
    (net (code "62") (name "Net-(D80-A)") (class "Default")
      (node (ref "D80") (pin "2") (pinfunction "A_2") (pintype "passive"))
      (node (ref "R337") (pin "1") (pinfunction "1_1") (pintype "passive"))
    )
    (net (code "63") (name "Net-(D81-A)") (class "Default")
      (node (ref "D81") (pin "2") (pinfunction "A_2") (pintype "passive"))
      (node (ref "R338") (pin "1") (pinfunction "1_1") (pintype "passive"))
    )
    (net (code "64") (name "Net-(Q26-B1)") (class "Default")
      (node (ref "Q26") (pin "5") (pinfunction "B1_5") (pintype "passive"))
      (node (ref "R301") (pin "1") (pinfunction "1_1") (pintype "passive"))
    )
    (net (code "65") (name "Net-(Q26-B2)") (class "Default")
      (node (ref "Q26") (pin "2") (pinfunction "B2_2") (pintype "passive"))
      (node (ref "R305") (pin "2") (pinfunction "2_2") (pintype "passive"))
    )
    (net (code "66") (name "Net-(Q26-C1)") (class "Default")
      (node (ref "Q26") (pin "6") (pinfunction "C1_6") (pintype "passive"))
      (node (ref "R294") (pin "1") (pinfunction "1_1") (pintype "passive"))
    )
    (net (code "67") (name "Net-(Q26-C2)") (class "Default")
      (node (ref "Q26") (pin "3") (pinfunction "C2_3") (pintype "passive"))
      (node (ref "R293") (pin "1") (pinfunction "1_1") (pintype "passive"))
    )
    (net (code "68") (name "Net-(Q27-B1)") (class "Default")
      (node (ref "Q27") (pin "5") (pinfunction "B1_5") (pintype "passive"))
      (node (ref "R302") (pin "1") (pinfunction "1_1") (pintype "passive"))
    )
    (net (code "69") (name "Net-(Q27-B2)") (class "Default")
      (node (ref "Q27") (pin "2") (pinfunction "B2_2") (pintype "passive"))
      (node (ref "R306") (pin "2") (pinfunction "2_2") (pintype "passive"))
    )
    (net (code "70") (name "Net-(Q27-C1)") (class "Default")
      (node (ref "Q27") (pin "6") (pinfunction "C1_6") (pintype "passive"))
      (node (ref "R296") (pin "1") (pinfunction "1_1") (pintype "passive"))
    )
    (net (code "71") (name "Net-(Q27-C2)") (class "Default")
      (node (ref "Q27") (pin "3") (pinfunction "C2_3") (pintype "passive"))
      (node (ref "R295") (pin "1") (pinfunction "1_1") (pintype "passive"))
    )
    (net (code "72") (name "Net-(Q28-B1)") (class "Default")
      (node (ref "Q28") (pin "5") (pinfunction "B1_5") (pintype "passive"))
      (node (ref "R303") (pin "1") (pinfunction "1_1") (pintype "passive"))
    )
    (net (code "73") (name "Net-(Q28-B2)") (class "Default")
      (node (ref "Q28") (pin "2") (pinfunction "B2_2") (pintype "passive"))
      (node (ref "R307") (pin "2") (pinfunction "2_2") (pintype "passive"))
    )
    (net (code "74") (name "Net-(Q28-C1)") (class "Default")
      (node (ref "Q28") (pin "6") (pinfunction "C1_6") (pintype "passive"))
      (node (ref "R298") (pin "1") (pinfunction "1_1") (pintype "passive"))
    )
    (net (code "75") (name "Net-(Q28-C2)") (class "Default")
      (node (ref "Q28") (pin "3") (pinfunction "C2_3") (pintype "passive"))
      (node (ref "R297") (pin "1") (pinfunction "1_1") (pintype "passive"))
    )
    (net (code "76") (name "Net-(Q29-B1)") (class "Default")
      (node (ref "Q29") (pin "5") (pinfunction "B1_5") (pintype "passive"))
      (node (ref "R304") (pin "1") (pinfunction "1_1") (pintype "passive"))
    )
    (net (code "77") (name "Net-(Q29-B2)") (class "Default")
      (node (ref "Q29") (pin "2") (pinfunction "B2_2") (pintype "passive"))
      (node (ref "R308") (pin "2") (pinfunction "2_2") (pintype "passive"))
    )
    (net (code "78") (name "Net-(Q29-C1)") (class "Default")
      (node (ref "Q29") (pin "6") (pinfunction "C1_6") (pintype "passive"))
      (node (ref "R300") (pin "1") (pinfunction "1_1") (pintype "passive"))
    )
    (net (code "79") (name "Net-(Q29-C2)") (class "Default")
      (node (ref "Q29") (pin "3") (pinfunction "C2_3") (pintype "passive"))
      (node (ref "R299") (pin "1") (pinfunction "1_1") (pintype "passive"))
    )
    (net (code "80") (name "Net-(Q30-B1)") (class "Default")
      (node (ref "Q30") (pin "5") (pinfunction "B1_5") (pintype "passive"))
      (node (ref "R317") (pin "1") (pinfunction "1_1") (pintype "passive"))
    )
    (net (code "81") (name "Net-(Q30-B2)") (class "Default")
      (node (ref "Q30") (pin "2") (pinfunction "B2_2") (pintype "passive"))
      (node (ref "R321") (pin "2") (pinfunction "2_2") (pintype "passive"))
    )
    (net (code "82") (name "Net-(Q30-C1)") (class "Default")
      (node (ref "Q30") (pin "6") (pinfunction "C1_6") (pintype "passive"))
      (node (ref "R310") (pin "1") (pinfunction "1_1") (pintype "passive"))
    )
    (net (code "83") (name "Net-(Q30-C2)") (class "Default")
      (node (ref "Q30") (pin "3") (pinfunction "C2_3") (pintype "passive"))
      (node (ref "R309") (pin "1") (pinfunction "1_1") (pintype "passive"))
    )
    (net (code "84") (name "Net-(Q31-B1)") (class "Default")
      (node (ref "Q31") (pin "5") (pinfunction "B1_5") (pintype "passive"))
      (node (ref "R318") (pin "1") (pinfunction "1_1") (pintype "passive"))
    )
    (net (code "85") (name "Net-(Q31-B2)") (class "Default")
      (node (ref "Q31") (pin "2") (pinfunction "B2_2") (pintype "passive"))
      (node (ref "R322") (pin "2") (pinfunction "2_2") (pintype "passive"))
    )
    (net (code "86") (name "Net-(Q31-C1)") (class "Default")
      (node (ref "Q31") (pin "6") (pinfunction "C1_6") (pintype "passive"))
      (node (ref "R312") (pin "1") (pinfunction "1_1") (pintype "passive"))
    )
    (net (code "87") (name "Net-(Q31-C2)") (class "Default")
      (node (ref "Q31") (pin "3") (pinfunction "C2_3") (pintype "passive"))
      (node (ref "R311") (pin "1") (pinfunction "1_1") (pintype "passive"))
    )
    (net (code "88") (name "Net-(Q32-B1)") (class "Default")
      (node (ref "Q32") (pin "5") (pinfunction "B1_5") (pintype "passive"))
      (node (ref "R319") (pin "1") (pinfunction "1_1") (pintype "passive"))
    )
    (net (code "89") (name "Net-(Q32-B2)") (class "Default")
      (node (ref "Q32") (pin "2") (pinfunction "B2_2") (pintype "passive"))
      (node (ref "R323") (pin "2") (pinfunction "2_2") (pintype "passive"))
    )
    (net (code "90") (name "Net-(Q32-C1)") (class "Default")
      (node (ref "Q32") (pin "6") (pinfunction "C1_6") (pintype "passive"))
      (node (ref "R314") (pin "1") (pinfunction "1_1") (pintype "passive"))
    )
    (net (code "91") (name "Net-(Q32-C2)") (class "Default")
      (node (ref "Q32") (pin "3") (pinfunction "C2_3") (pintype "passive"))
      (node (ref "R313") (pin "1") (pinfunction "1_1") (pintype "passive"))
    )
    (net (code "92") (name "Net-(Q33-B1)") (class "Default")
      (node (ref "Q33") (pin "5") (pinfunction "B1_5") (pintype "passive"))
      (node (ref "R320") (pin "1") (pinfunction "1_1") (pintype "passive"))
    )
    (net (code "93") (name "Net-(Q33-B2)") (class "Default")
      (node (ref "Q33") (pin "2") (pinfunction "B2_2") (pintype "passive"))
      (node (ref "R324") (pin "2") (pinfunction "2_2") (pintype "passive"))
    )
    (net (code "94") (name "Net-(Q33-C1)") (class "Default")
      (node (ref "Q33") (pin "6") (pinfunction "C1_6") (pintype "passive"))
      (node (ref "R316") (pin "1") (pinfunction "1_1") (pintype "passive"))
    )
    (net (code "95") (name "Net-(Q33-C2)") (class "Default")
      (node (ref "Q33") (pin "3") (pinfunction "C2_3") (pintype "passive"))
      (node (ref "R315") (pin "1") (pinfunction "1_1") (pintype "passive"))
    )
    (net (code "96") (name "Net-(Q34-B1)") (class "Default")
      (node (ref "Q34") (pin "5") (pinfunction "B1_5") (pintype "passive"))
      (node (ref "R329") (pin "1") (pinfunction "1_1") (pintype "passive"))
    )
    (net (code "97") (name "Net-(Q34-B2)") (class "Default")
      (node (ref "Q34") (pin "2") (pinfunction "B2_2") (pintype "passive"))
      (node (ref "R331") (pin "2") (pinfunction "2_2") (pintype "passive"))
    )
    (net (code "98") (name "Net-(Q34-C1)") (class "Default")
      (node (ref "Q34") (pin "6") (pinfunction "C1_6") (pintype "passive"))
      (node (ref "R326") (pin "1") (pinfunction "1_1") (pintype "passive"))
    )
    (net (code "99") (name "Net-(Q34-C2)") (class "Default")
      (node (ref "Q34") (pin "3") (pinfunction "C2_3") (pintype "passive"))
      (node (ref "R325") (pin "1") (pinfunction "1_1") (pintype "passive"))
    )
    (net (code "100") (name "Net-(Q35-B1)") (class "Default")
      (node (ref "Q35") (pin "5") (pinfunction "B1_5") (pintype "passive"))
      (node (ref "R330") (pin "1") (pinfunction "1_1") (pintype "passive"))
    )
    (net (code "101") (name "Net-(Q35-B2)") (class "Default")
      (node (ref "Q35") (pin "2") (pinfunction "B2_2") (pintype "passive"))
      (node (ref "R332") (pin "2") (pinfunction "2_2") (pintype "passive"))
    )
    (net (code "102") (name "Net-(Q35-C1)") (class "Default")
      (node (ref "Q35") (pin "6") (pinfunction "C1_6") (pintype "passive"))
      (node (ref "R328") (pin "1") (pinfunction "1_1") (pintype "passive"))
    )
    (net (code "103") (name "Net-(Q35-C2)") (class "Default")
      (node (ref "Q35") (pin "3") (pinfunction "C2_3") (pintype "passive"))
      (node (ref "R327") (pin "1") (pinfunction "1_1") (pintype "passive"))
    )
    (net (code "104") (name "Net-(Q36-B1)") (class "Default")
      (node (ref "Q36") (pin "2") (pinfunction "B1_2") (pintype "passive"))
      (node (ref "R335") (pin "1") (pinfunction "1_1") (pintype "passive"))
    )
    (net (code "105") (name "Net-(Q36-B2)") (class "Default")
      (node (ref "Q36") (pin "5") (pinfunction "B2_5") (pintype "passive"))
      (node (ref "R333") (pin "2") (pinfunction "2_2") (pintype "passive"))
    )
    (net (code "106") (name "Net-(Q36-C1)") (class "Default")
      (node (ref "Q36") (pin "6") (pinfunction "C1_6") (pintype "passive"))
      (node (ref "R336") (pin "2") (pinfunction "2_2") (pintype "passive"))
    )
    (net (code "107") (name "Net-(Q36-C2)") (class "Default")
      (node (ref "Q36") (pin "3") (pinfunction "C2_3") (pintype "passive"))
      (node (ref "R337") (pin "2") (pinfunction "2_2") (pintype "passive"))
    )
    (net (code "108") (name "Net-(Q37-B2)") (class "Default")
      (node (ref "Q37") (pin "5") (pinfunction "B2_5") (pintype "passive"))
      (node (ref "R334") (pin "2") (pinfunction "2_2") (pintype "passive"))
    )
    (net (code "109") (name "Net-(Q37-C1)") (class "Default")
      (node (ref "Q37") (pin "6") (pinfunction "C1_6") (pintype "passive"))
      (node (ref "R338") (pin "2") (pinfunction "2_2") (pintype "passive"))
    )
    (net (code "110") (name "TRB_GND") (class "Default")
      (node (ref "D79") (pin "1") (pinfunction "K_1") (pintype "passive"))
      (node (ref "D80") (pin "1") (pinfunction "K_1") (pintype "passive"))
      (node (ref "D81") (pin "1") (pinfunction "K_1") (pintype "passive"))
      (node (ref "Q26") (pin "1") (pinfunction "E1_1") (pintype "passive"))
      (node (ref "Q26") (pin "4") (pinfunction "E2_4") (pintype "passive"))
      (node (ref "Q27") (pin "1") (pinfunction "E1_1") (pintype "passive"))
      (node (ref "Q27") (pin "4") (pinfunction "E2_4") (pintype "passive"))
      (node (ref "Q28") (pin "1") (pinfunction "E1_1") (pintype "passive"))
      (node (ref "Q28") (pin "4") (pinfunction "E2_4") (pintype "passive"))
      (node (ref "Q29") (pin "1") (pinfunction "E1_1") (pintype "passive"))
      (node (ref "Q29") (pin "4") (pinfunction "E2_4") (pintype "passive"))
      (node (ref "Q30") (pin "1") (pinfunction "E1_1") (pintype "passive"))
      (node (ref "Q30") (pin "4") (pinfunction "E2_4") (pintype "passive"))
      (node (ref "Q31") (pin "1") (pinfunction "E1_1") (pintype "passive"))
      (node (ref "Q31") (pin "4") (pinfunction "E2_4") (pintype "passive"))
      (node (ref "Q32") (pin "1") (pinfunction "E1_1") (pintype "passive"))
      (node (ref "Q32") (pin "4") (pinfunction "E2_4") (pintype "passive"))
      (node (ref "Q33") (pin "1") (pinfunction "E1_1") (pintype "passive"))
      (node (ref "Q33") (pin "4") (pinfunction "E2_4") (pintype "passive"))
      (node (ref "Q34") (pin "1") (pinfunction "E1_1") (pintype "passive"))
      (node (ref "Q34") (pin "4") (pinfunction "E2_4") (pintype "passive"))
      (node (ref "Q35") (pin "1") (pinfunction "E1_1") (pintype "passive"))
      (node (ref "Q35") (pin "4") (pinfunction "E2_4") (pintype "passive"))
    )
    (net (code "111") (name "unconnected-(Q37-B1-Pad2)") (class "Default")
      (node (ref "Q37") (pin "2") (pinfunction "B1_2") (pintype "passive+no_connect"))
    )
    (net (code "112") (name "unconnected-(Q37-C2-Pad3)") (class "Default")
      (node (ref "Q37") (pin "3") (pinfunction "C2_3") (pintype "passive+no_connect"))
    )
  )
)
